# Power_Supply.net
KiCad netlist of a schematic drawn in Altium Designer
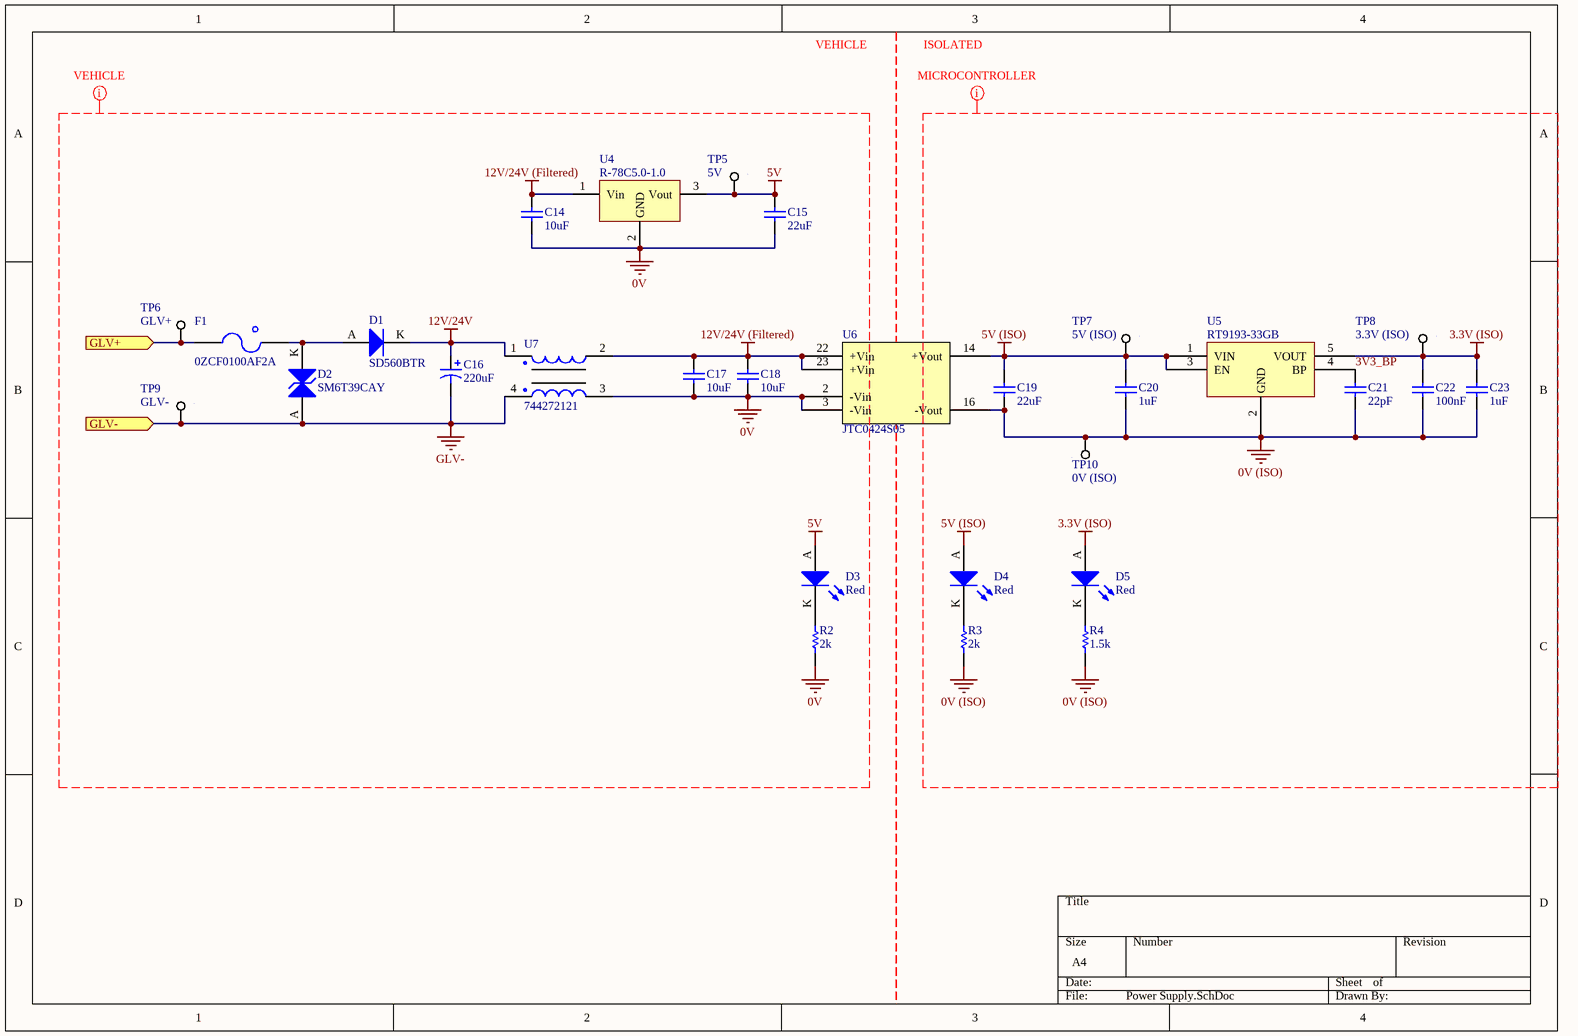
[diagram p0: Power Supply.SchDoc]

(export (version "E")
  (design (tool "Eeschema 10.0.6"))
  (components
    (comp (ref "C14")
      (value "10uF")
      (footprint "0805")
      (fields
        (field (name "PART NUMBER") "GRM21BR6YA106KE43L")
        (field (name "TOLERANCE") "10%")
        (field (name "MANUFACTURER") "muRata")
      )
      (libsource (lib "ts_20-standard-library") (part "Capacitor"))
    )
    (comp (ref "C15")
      (value "22uF")
      (footprint "1206")
      (fields
        (field (name "PART NUMBER") "CC1206MKX5R7BB226")
        (field (name "TOLERANCE") "20%")
        (field (name "MANUFACTURER") "YAGEO")
      )
      (libsource (lib "ts_20-standard-library") (part "Capacitor"))
    )
    (comp (ref "C16")
      (value "~")
      (footprint "Vishay Radial 1213")
      (fields
        (field (name "PART NUMBER") "MAL214699106E3")
        (field (name "TOLERANCE") "20%")
        (field (name "MANUFACTURER") "Vishay")
      )
      (libsource (lib "ts_20-standard-library") (part "Capacitor (Polarised)"))
    )
    (comp (ref "C17")
      (value "10uF")
      (footprint "0805")
      (fields
        (field (name "PART NUMBER") "GRM21BR6YA106KE43L")
        (field (name "TOLERANCE") "10%")
        (field (name "MANUFACTURER") "muRata")
      )
      (libsource (lib "ts_20-standard-library") (part "Capacitor"))
    )
    (comp (ref "C18")
      (value "10uF")
      (footprint "0805")
      (fields
        (field (name "PART NUMBER") "GRM21BR6YA106KE43L")
        (field (name "TOLERANCE") "10%")
        (field (name "MANUFACTURER") "muRata")
      )
      (libsource (lib "ts_20-standard-library") (part "Capacitor"))
    )
    (comp (ref "C19")
      (value "22uF")
      (footprint "1206")
      (fields
        (field (name "PART NUMBER") "CC1206MKX5R7BB226")
        (field (name "TOLERANCE") "20%")
        (field (name "MANUFACTURER") "YAGEO")
      )
      (libsource (lib "ts_20-standard-library") (part "Capacitor"))
    )
    (comp (ref "C20")
      (value "1uF")
      (footprint "0805")
      (fields
        (field (name "PART NUMBER") "AC0805KKX7R8BB105")
        (field (name "TOLERANCE") "10%")
        (field (name "MANUFACTURER") "YAGEO")
      )
      (libsource (lib "ts_20-standard-library") (part "Capacitor"))
    )
    (comp (ref "C21")
      (value "22pF")
      (footprint "0805")
      (fields
        (field (name "PART NUMBER") "GRM21A5C2E220JW01D")
        (field (name "TOLERANCE") "±5%")
        (field (name "MANUFACTURER") "muRata")
      )
      (libsource (lib "ts_20-standard-library") (part "Capacitor"))
    )
    (comp (ref "C22")
      (value "100nF")
      (footprint "0805")
      (fields
        (field (name "PART NUMBER") "GCM21BR71H104KA37L")
        (field (name "TOLERANCE") "±10%")
        (field (name "MANUFACTURER") "muRata")
      )
      (libsource (lib "ts_20-standard-library") (part "Capacitor"))
    )
    (comp (ref "C23")
      (value "1uF")
      (footprint "0805")
      (fields
        (field (name "PART NUMBER") "AC0805KKX7R8BB105")
        (field (name "TOLERANCE") "10%")
        (field (name "MANUFACTURER") "YAGEO")
      )
      (libsource (lib "ts_20-standard-library") (part "Capacitor"))
    )
    (comp (ref "D1")
      (value "SD560BTR")
      (footprint "SMB Diode")
      (description "1.2V_F 600V 5A SMB")
      (fields
        (field (name "MANUFACTURER") "SMC Diode Solutions")
        (field (name "DIGIKEY PART NUMBER") "1655-1530-2-ND")
      )
      (libsource (lib "ts_20-standard-library") (part "Diode"))
    )
    (comp (ref "D2")
      (value "SM6T39CAY")
      (footprint "ST SMB Diode")
      (description "42.8V Clamp 93A (8/20µs) Ipp Tvs Diode Surface Mount SMB (DO-214AA)")
      (fields (field (name "MANUFACTURER") "ST"))
      (libsource (lib "ts_20-standard-library") (part "Bidirectional Zener Diode"))
    )
    (comp (ref "D3")
      (value "Red")
      (footprint "0805 LED")
      (description "Red LED Indication - Discrete 1.75V 0805 (2012 Metric)")
      (fields (field (name "PART NUMBER") "SML-210LTT86") (field (name "MANUFACTURER") "ROHM Semiconductor"))
      (libsource (lib "ts_20-standard-library") (part "LED"))
    )
    (comp (ref "D4")
      (value "Red")
      (footprint "0805 LED")
      (description "Red LED Indication - Discrete 1.75V 0805 (2012 Metric)")
      (fields (field (name "PART NUMBER") "SML-210LTT86") (field (name "MANUFACTURER") "ROHM Semiconductor"))
      (libsource (lib "ts_20-standard-library") (part "LED"))
    )
    (comp (ref "D5")
      (value "Red")
      (footprint "0805 LED")
      (description "Red LED Indication - Discrete 1.75V 0805 (2012 Metric)")
      (fields (field (name "PART NUMBER") "SML-210LTT86") (field (name "MANUFACTURER") "ROHM Semiconductor"))
      (libsource (lib "ts_20-standard-library") (part "LED"))
    )
    (comp (ref "F1")
      (value "0ZCF0100AF2A")
      (footprint "2920")
      (description "PTC RESET FUSE 60V 1A 292")
      (fields
        (field (name "MANUFACTURER") "Littelfuse Inc.")
        (field (name "DIGIKEY PART NUMBER") "507-2070-1-ND")
      )
      (libsource (lib "ts_20-standard-library") (part "PTC Fuse"))
    )
    (comp (ref "R2")
      (value "2k")
      (footprint "0805")
      (fields
        (field (name "PART NUMBER") "RC0805FR072KL")
        (field (name "MANUFACTURER") "YAGEO")
        (field (name "TOLERANCE") "0.01")
      )
      (libsource (lib "ts_20-standard-library") (part "Resistor"))
    )
    (comp (ref "R3")
      (value "2k")
      (footprint "0805")
      (fields
        (field (name "PART NUMBER") "RC0805FR072KL")
        (field (name "MANUFACTURER") "YAGEO")
        (field (name "TOLERANCE") "0.01")
      )
      (libsource (lib "ts_20-standard-library") (part "Resistor"))
    )
    (comp (ref "R4")
      (value "1.5k")
      (footprint "0805")
      (fields
        (field (name "PART NUMBER") "RC0805FR071K5L")
        (field (name "MANUFACTURER") "YAGEO")
        (field (name "TOLERANCE") "0.01")
      )
      (libsource (lib "ts_20-standard-library") (part "Resistor"))
    )
    (comp (ref "TP5")
      (value "5V")
      (footprint "SMD Test Point 1mm")
      (fields (field (name "PART NUMBER") "SMD Test Point Small") (field (name "CONTACT") "NA"))
      (libsource (lib "ts_20-standard-connectors") (part "Test Point Small"))
    )
    (comp (ref "TP6")
      (value "GLV+")
      (footprint "SMD Test Point 1mm")
      (fields (field (name "PART NUMBER") "SMD Test Point Small") (field (name "CONTACT") "NA"))
      (libsource (lib "ts_20-standard-connectors") (part "Test Point Small"))
    )
    (comp (ref "TP7")
      (value "5V (ISO)")
      (footprint "SMD Test Point 1mm")
      (fields (field (name "PART NUMBER") "SMD Test Point Small") (field (name "CONTACT") "NA"))
      (libsource (lib "ts_20-standard-connectors") (part "Test Point Small"))
    )
    (comp (ref "TP8")
      (value "3.3V (ISO)")
      (footprint "SMD Test Point 1mm")
      (fields (field (name "PART NUMBER") "SMD Test Point Small") (field (name "CONTACT") "NA"))
      (libsource (lib "ts_20-standard-connectors") (part "Test Point Small"))
    )
    (comp (ref "TP9")
      (value "GLV-")
      (footprint "SMD Test Point 1mm")
      (fields (field (name "PART NUMBER") "SMD Test Point Small") (field (name "CONTACT") "NA"))
      (libsource (lib "ts_20-standard-connectors") (part "Test Point Small"))
    )
    (comp (ref "TP10")
      (value "0V (ISO)")
      (footprint "SMD Test Point 1mm")
      (fields (field (name "PART NUMBER") "SMD Test Point Small") (field (name "CONTACT") "NA"))
      (libsource (lib "ts_20-standard-connectors") (part "Test Point Small"))
    )
    (comp (ref "U4")
      (value "R-78C5.0-1.0")
      (footprint "RECOM 3-SIP")
      (description "CONV DC/DC 1A 5V OUT SIP VERT")
      (fields (field (name "MANUFACTURER") "Recom") (field (name "DIGIKEY PART NUMBER") "945-1395-5-ND"))
      (libsource (lib "ts_20-standard-library") (part "R-78C5.0-1.0"))
    )
    (comp (ref "U5")
      (value "RT9193-33GB")
      (footprint "RICHTEK SOT-23-5")
      (description "Linear Voltage Regulator IC 1 Output 300mA SOT-23-5")
      (fields (field (name "MANUFACTURER") "Richtek") (field (name "DIGIKEY PART NUMBER") "1028-1014-1-ND"))
      (libsource (lib "ts_20-standard-library") (part "RT9193-33GB"))
    )
    (comp (ref "U6")
      (value "JTC0424S05")
      (footprint "24-DIP Module, 7 Leads")
      (description "DC DC CONVERTER 5V 4W")
      (fields (field (name "MANUFACTURER") "XP Power") (field (name "DIGIKEY PART NUMBER") "JTC0424S05-ND"))
      (libsource (lib "ts_20-standard-library") (part "JTC0424S05"))
    )
    (comp (ref "U7")
      (value "744272121")
      (footprint "Wurth 4-PC Pad")
      (description "120µH @ 100kHz 2 Line Common Mode Choke Surface Mount 460 Ohms @ 30MHz 2.5A DCR 25mOhm")
      (fields
        (field (name "MANUFACTURER") "Wurth Electronics Inc")
        (field (name "DIGIKEY PART NUMBER") "732-1489-1-ND")
      )
      (libsource (lib "ts_20-standard-library") (part "744272121"))
    )
  )
  (nets
    (net (code "1") (name "/3V3_BP") (class "Default")
      (node (ref "C21") (pin "2") (pinfunction "2_2") (pintype "passive"))
      (node (ref "U5") (pin "4") (pinfunction "BP_4") (pintype "passive"))
    )
    (net (code "2") (name "/GLV+") (class "Default")
      (node (ref "F1") (pin "1") (pinfunction "1_1") (pintype "passive"))
      (node (ref "TP6") (pin "1") (pinfunction "1_1") (pintype "passive"))
    )
    (net (code "3") (name "0V") (class "Default")
      (node (ref "C14") (pin "1") (pinfunction "1_1") (pintype "passive"))
      (node (ref "C15") (pin "1") (pinfunction "1_1") (pintype "passive"))
      (node (ref "C17") (pin "1") (pinfunction "1_1") (pintype "passive"))
      (node (ref "C18") (pin "1") (pinfunction "1_1") (pintype "passive"))
      (node (ref "R2") (pin "1") (pinfunction "1_1") (pintype "passive"))
      (node (ref "U4") (pin "2") (pinfunction "GND_2") (pintype "passive"))
      (node (ref "U6") (pin "2") (pinfunction "-Vin_2") (pintype "passive"))
      (node (ref "U6") (pin "3") (pinfunction "-Vin_3") (pintype "passive"))
      (node (ref "U7") (pin "3") (pinfunction "3_3") (pintype "power_in"))
    )
    (net (code "4") (name "0V (ISO)") (class "Default")
      (node (ref "C19") (pin "1") (pinfunction "1_1") (pintype "passive"))
      (node (ref "C20") (pin "1") (pinfunction "1_1") (pintype "passive"))
      (node (ref "C21") (pin "1") (pinfunction "1_1") (pintype "passive"))
      (node (ref "C22") (pin "1") (pinfunction "1_1") (pintype "passive"))
      (node (ref "C23") (pin "1") (pinfunction "1_1") (pintype "passive"))
      (node (ref "R3") (pin "1") (pinfunction "1_1") (pintype "passive"))
      (node (ref "R4") (pin "1") (pinfunction "1_1") (pintype "passive"))
      (node (ref "TP10") (pin "1") (pinfunction "1_1") (pintype "passive"))
      (node (ref "U5") (pin "2") (pinfunction "GND_2") (pintype "passive"))
      (node (ref "U6") (pin "16") (pinfunction "-Vout_16") (pintype "passive"))
    )
    (net (code "5") (name "3.3V (ISO)") (class "Default")
      (node (ref "C22") (pin "2") (pinfunction "2_2") (pintype "passive"))
      (node (ref "C23") (pin "2") (pinfunction "2_2") (pintype "passive"))
      (node (ref "D5") (pin "A") (pinfunction "A_A") (pintype "passive"))
      (node (ref "TP8") (pin "1") (pinfunction "1_1") (pintype "passive"))
      (node (ref "U5") (pin "5") (pinfunction "VOUT_5") (pintype "passive"))
    )
    (net (code "6") (name "5V") (class "Default")
      (node (ref "C15") (pin "2") (pinfunction "2_2") (pintype "passive"))
      (node (ref "D3") (pin "A") (pinfunction "A_A") (pintype "passive"))
      (node (ref "TP5") (pin "1") (pinfunction "1_1") (pintype "passive"))
      (node (ref "U4") (pin "3") (pinfunction "Vout_3") (pintype "passive"))
    )
    (net (code "7") (name "5V (ISO)") (class "Default")
      (node (ref "C19") (pin "2") (pinfunction "2_2") (pintype "passive"))
      (node (ref "C20") (pin "2") (pinfunction "2_2") (pintype "passive"))
      (node (ref "D4") (pin "A") (pinfunction "A_A") (pintype "passive"))
      (node (ref "TP7") (pin "1") (pinfunction "1_1") (pintype "passive"))
      (node (ref "U5") (pin "1") (pinfunction "VIN_1") (pintype "passive"))
      (node (ref "U5") (pin "3") (pinfunction "EN_3") (pintype "passive"))
      (node (ref "U6") (pin "14") (pinfunction "+Vout_14") (pintype "passive"))
    )
    (net (code "8") (name "12V{slash}24V") (class "Default")
      (node (ref "C16") (pin "2") (pinfunction "2_2") (pintype "passive"))
      (node (ref "D1") (pin "K") (pinfunction "K_K") (pintype "passive"))
      (node (ref "U7") (pin "1") (pinfunction "1_1") (pintype "passive"))
    )
    (net (code "9") (name "12V{slash}24V (Filtered)") (class "Default")
      (node (ref "C14") (pin "2") (pinfunction "2_2") (pintype "passive"))
      (node (ref "C17") (pin "2") (pinfunction "2_2") (pintype "passive"))
      (node (ref "C18") (pin "2") (pinfunction "2_2") (pintype "passive"))
      (node (ref "U4") (pin "1") (pinfunction "Vin_1") (pintype "passive"))
      (node (ref "U6") (pin "22") (pinfunction "+Vin_22") (pintype "passive"))
      (node (ref "U6") (pin "23") (pinfunction "+Vin_23") (pintype "passive"))
      (node (ref "U7") (pin "2") (pinfunction "2_2") (pintype "passive"))
    )
    (net (code "10") (name "GLV-") (class "Default")
      (node (ref "C16") (pin "1") (pinfunction "1_1") (pintype "passive"))
      (node (ref "D2") (pin "A") (pinfunction "A_A") (pintype "passive"))
      (node (ref "TP9") (pin "1") (pinfunction "1_1") (pintype "passive"))
      (node (ref "U7") (pin "4") (pinfunction "4_4") (pintype "passive"))
    )
    (net (code "11") (name "Net-(D1-PadA)") (class "Default")
      (node (ref "D1") (pin "A") (pinfunction "A_A") (pintype "passive"))
      (node (ref "D2") (pin "K") (pinfunction "K_K") (pintype "passive"))
      (node (ref "F1") (pin "2") (pinfunction "2_2") (pintype "passive"))
    )
    (net (code "12") (name "Net-(D3-PadK)") (class "Default")
      (node (ref "D3") (pin "K") (pinfunction "K_K") (pintype "passive"))
      (node (ref "R2") (pin "2") (pinfunction "2_2") (pintype "passive"))
    )
    (net (code "13") (name "Net-(D4-PadK)") (class "Default")
      (node (ref "D4") (pin "K") (pinfunction "K_K") (pintype "passive"))
      (node (ref "R3") (pin "2") (pinfunction "2_2") (pintype "passive"))
    )
    (net (code "14") (name "Net-(D5-PadK)") (class "Default")
      (node (ref "D5") (pin "K") (pinfunction "K_K") (pintype "passive"))
      (node (ref "R4") (pin "2") (pinfunction "2_2") (pintype "passive"))
    )
  )
)
